# ArduinoSmarticle.net
KiCad netlist of a schematic drawn in EAGLE
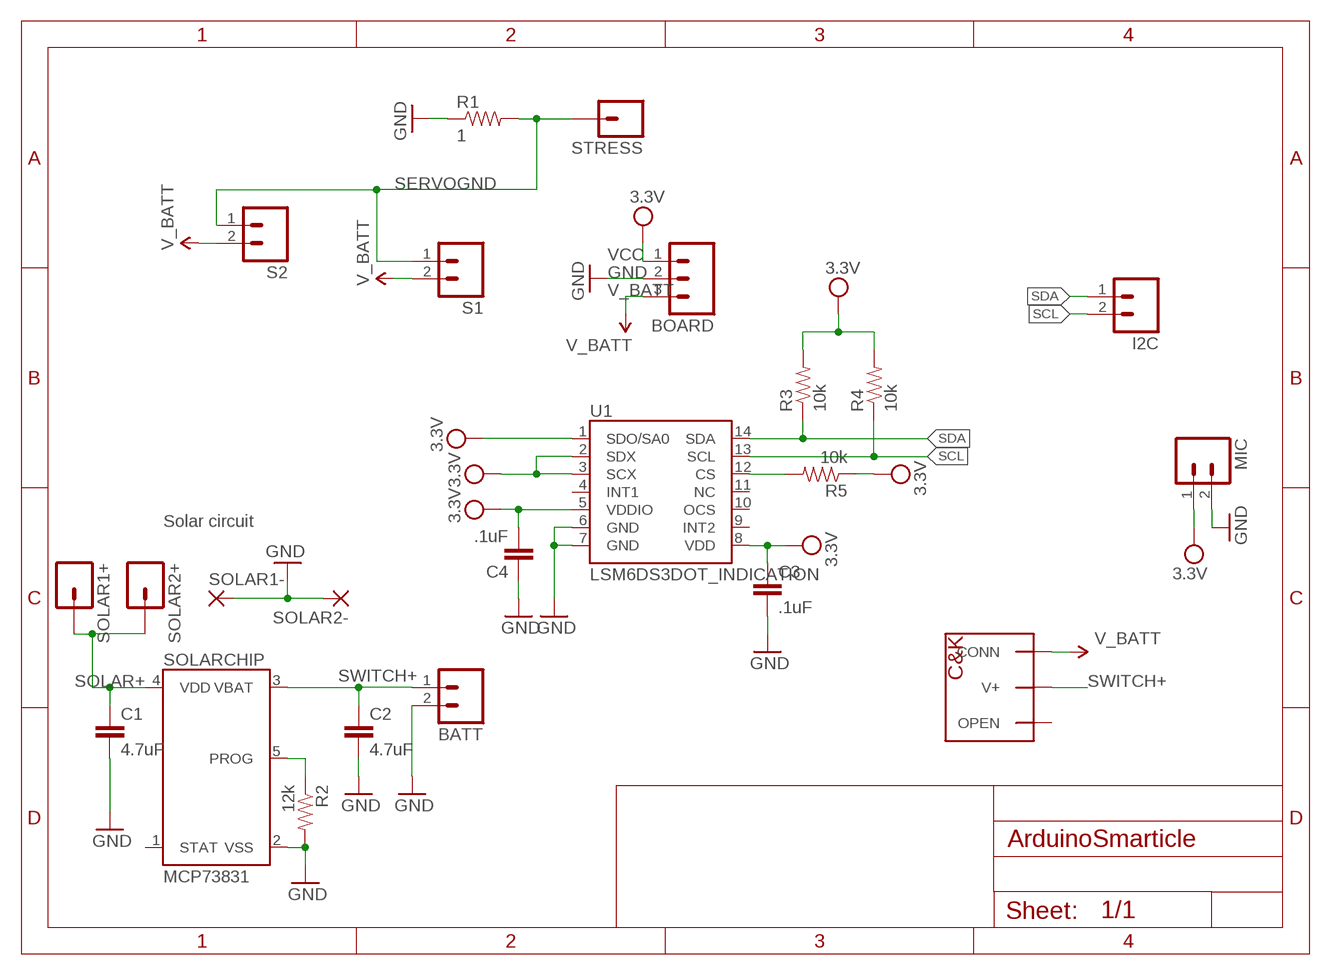
[diagram p0: schematic, sheet 1]

(export (version "E")
  (design (tool "Eeschema 10.0.6"))
  (components
    (comp (ref "BATT")
      (value "M02PTH")
      (footprint "eagle-import:1X02")
      (libsource (lib "eagle-import") (part "M02PTH"))
    )
    (comp (ref "BOARD")
      (value "M03PTH")
      (footprint "eagle-import:1X03")
      (libsource (lib "eagle-import") (part "M03PTH"))
    )
    (comp (ref "C1")
      (value "4.7uF")
      (footprint "eagle-import:0603-CAP")
      (libsource (lib "eagle-import") (part "4.7UF-6.3V-10%(0603)0603"))
    )
    (comp (ref "C2")
      (value "4.7uF")
      (footprint "eagle-import:0603-CAP")
      (libsource (lib "eagle-import") (part "4.7UF-6.3V-10%(0603)0603"))
    )
    (comp (ref "C3")
      (value ".1uF")
      (footprint "eagle-import:0603-CAP")
      (libsource (lib "eagle-import") (part "4.7UF-6.3V-10%(0603)0603"))
    )
    (comp (ref "C4")
      (value ".1uF")
      (footprint "eagle-import:0603-CAP")
      (libsource (lib "eagle-import") (part "4.7UF-6.3V-10%(0603)0603"))
    )
    (comp (ref "I2C")
      (value "M02PTH")
      (footprint "eagle-import:1X02")
      (libsource (lib "eagle-import") (part "M02PTH"))
    )
    (comp (ref "MIC")
      (value "M02PTH")
      (footprint "eagle-import:1X02")
      (libsource (lib "eagle-import") (part "M02PTH"))
    )
    (comp (ref "R1")
      (value "1")
      (footprint "eagle-import:0603-RES")
      (libsource (lib "eagle-import") (part "2.0KOHM1/10W5%(0603)"))
    )
    (comp (ref "R2")
      (value "12k")
      (footprint "eagle-import:0603")
      (libsource (lib "eagle-import") (part "10.5KOHM1/10W1%(0603)"))
    )
    (comp (ref "R3")
      (value "10k")
      (footprint "eagle-import:0603-RES")
      (libsource (lib "eagle-import") (part "4.7KOHM-1/10W-1%(0603)"))
    )
    (comp (ref "R4")
      (value "10k")
      (footprint "eagle-import:0603-RES")
      (libsource (lib "eagle-import") (part "4.7KOHM-1/10W-1%(0603)"))
    )
    (comp (ref "R5")
      (value "10k")
      (footprint "eagle-import:0603-RES")
      (libsource (lib "eagle-import") (part "4.7KOHM-1/10W-1%(0603)"))
    )
    (comp (ref "S1")
      (value "M02PTH")
      (footprint "eagle-import:1X02")
      (libsource (lib "eagle-import") (part "M02PTH"))
    )
    (comp (ref "S2")
      (value "M02PTH")
      (footprint "eagle-import:1X02")
      (libsource (lib "eagle-import") (part "M02PTH"))
    )
    (comp (ref "SOLAR1+")
      (value "M01PTH")
      (footprint "eagle-import:1X01")
      (libsource (lib "eagle-import") (part "M01PTH"))
    )
    (comp (ref "SOLAR1-")
      (value "1,6/0,9")
      (footprint "eagle-import:1,6_0,9")
      (libsource (lib "eagle-import") (part "1,6/0,9"))
    )
    (comp (ref "SOLAR2+")
      (value "M01PTH")
      (footprint "eagle-import:1X01")
      (libsource (lib "eagle-import") (part "M01PTH"))
    )
    (comp (ref "SOLAR2-")
      (value "1,6/0,9")
      (footprint "eagle-import:1,6_0,9")
      (libsource (lib "eagle-import") (part "1,6/0,9"))
    )
    (comp (ref "SOLARCHIP")
      (value "MCP73831")
      (footprint "eagle-import:SOT23-5")
      (libsource (lib "eagle-import") (part "MCP73831"))
    )
    (comp (ref "STRESS")
      (value "M01PTH")
      (footprint "eagle-import:1X01")
      (libsource (lib "eagle-import") (part "M01PTH"))
    )
    (comp (ref "U$1")
      (value "WILL-BLACKSLIDESWITCH")
      (footprint "eagle-import:WILL-BLACKSLIDESWITCH")
      (libsource (lib "eagle-import") (part "WILL-BLACKSLIDESWITCH"))
    )
    (comp (ref "U1")
      (value "LSM6DS3DOT_INDICATION")
      (footprint "eagle-import:LGA14L_DOT_INDICATOR")
      (libsource (lib "eagle-import") (part "LSM6DS3DOT_INDICATION"))
    )
  )
  (nets
    (net (code "1") (name "/SERVOGND") (class "Default")
      (node (ref "R1") (pin "2") (pinfunction "2_2") (pintype "passive"))
      (node (ref "S1") (pin "1") (pinfunction "1_1") (pintype "passive"))
      (node (ref "S2") (pin "1") (pinfunction "1_1") (pintype "passive"))
      (node (ref "STRESS") (pin "1") (pinfunction "1_1") (pintype "passive"))
    )
    (net (code "2") (name "/SOLAR+") (class "Default")
      (node (ref "C1") (pin "1") (pinfunction "1_1") (pintype "passive"))
      (node (ref "SOLAR1+") (pin "1") (pinfunction "1_1") (pintype "passive"))
      (node (ref "SOLAR2+") (pin "1") (pinfunction "1_1") (pintype "passive"))
      (node (ref "SOLARCHIP") (pin "4") (pinfunction "VDD_4") (pintype "power_in"))
    )
    (net (code "3") (name "/SWITCH+") (class "Default")
      (node (ref "BATT") (pin "1") (pinfunction "1_1") (pintype "passive"))
      (node (ref "C2") (pin "1") (pinfunction "1_1") (pintype "passive"))
      (node (ref "SOLARCHIP") (pin "3") (pinfunction "VBAT_3") (pintype "power_in"))
      (node (ref "U$1") (pin "V+") (pinfunction "V+_V+") (pintype "bidirectional"))
    )
    (net (code "4") (name "3.3V") (class "Default")
      (node (ref "BOARD") (pin "1") (pinfunction "1_1") (pintype "passive"))
      (node (ref "C3") (pin "1") (pinfunction "1_1") (pintype "passive"))
      (node (ref "C4") (pin "2") (pinfunction "2_2") (pintype "passive"))
      (node (ref "MIC") (pin "1") (pinfunction "1_1") (pintype "passive"))
      (node (ref "R3") (pin "2") (pinfunction "2_2") (pintype "passive"))
      (node (ref "R4") (pin "2") (pinfunction "2_2") (pintype "passive"))
      (node (ref "R5") (pin "1") (pinfunction "1_1") (pintype "passive"))
      (node (ref "U1") (pin "1") (pinfunction "SDO/SA0_1") (pintype "bidirectional"))
      (node (ref "U1") (pin "2") (pinfunction "SDX_2") (pintype "bidirectional"))
      (node (ref "U1") (pin "3") (pinfunction "SCX_3") (pintype "bidirectional"))
      (node (ref "U1") (pin "5") (pinfunction "VDDIO_5") (pintype "bidirectional"))
      (node (ref "U1") (pin "8") (pinfunction "VDD_8") (pintype "bidirectional"))
    )
    (net (code "5") (name "GND") (class "Default")
      (node (ref "BATT") (pin "2") (pinfunction "2_2") (pintype "passive"))
      (node (ref "BOARD") (pin "2") (pinfunction "2_2") (pintype "passive"))
      (node (ref "C1") (pin "2") (pinfunction "2_2") (pintype "passive"))
      (node (ref "C2") (pin "2") (pinfunction "2_2") (pintype "passive"))
      (node (ref "C3") (pin "2") (pinfunction "2_2") (pintype "passive"))
      (node (ref "C4") (pin "1") (pinfunction "1_1") (pintype "passive"))
      (node (ref "MIC") (pin "2") (pinfunction "2_2") (pintype "passive"))
      (node (ref "R1") (pin "1") (pinfunction "1_1") (pintype "passive"))
      (node (ref "R2") (pin "2") (pinfunction "2_2") (pintype "passive"))
      (node (ref "SOLAR1-") (pin "1") (pinfunction "P_1") (pintype "passive"))
      (node (ref "SOLAR2-") (pin "1") (pinfunction "P_1") (pintype "passive"))
      (node (ref "SOLARCHIP") (pin "2") (pinfunction "VSS_2") (pintype "power_in"))
      (node (ref "U1") (pin "6") (pinfunction "GND_6") (pintype "bidirectional"))
      (node (ref "U1") (pin "7") (pinfunction "GND_7") (pintype "bidirectional"))
    )
    (net (code "6") (name "Net-(SOLARCHIP-PROG)") (class "Default")
      (node (ref "R2") (pin "1") (pinfunction "1_1") (pintype "passive"))
      (node (ref "SOLARCHIP") (pin "5") (pinfunction "PROG_5") (pintype "input"))
    )
    (net (code "7") (name "Net-(U1-CS)") (class "Default")
      (node (ref "R5") (pin "2") (pinfunction "2_2") (pintype "passive"))
      (node (ref "U1") (pin "12") (pinfunction "CS_12") (pintype "bidirectional"))
    )
    (net (code "8") (name "SCL") (class "Default")
      (node (ref "I2C") (pin "2") (pinfunction "2_2") (pintype "passive"))
      (node (ref "R4") (pin "1") (pinfunction "1_1") (pintype "passive"))
      (node (ref "U1") (pin "13") (pinfunction "SCL_13") (pintype "bidirectional"))
    )
    (net (code "9") (name "SDA") (class "Default")
      (node (ref "I2C") (pin "1") (pinfunction "1_1") (pintype "passive"))
      (node (ref "R3") (pin "1") (pinfunction "1_1") (pintype "passive"))
      (node (ref "U1") (pin "14") (pinfunction "SDA_14") (pintype "bidirectional"))
    )
    (net (code "10") (name "V_BATT") (class "Default")
      (node (ref "BOARD") (pin "3") (pinfunction "3_3") (pintype "passive"))
      (node (ref "S1") (pin "2") (pinfunction "2_2") (pintype "passive"))
      (node (ref "S2") (pin "2") (pinfunction "2_2") (pintype "passive"))
      (node (ref "U$1") (pin "CONN") (pinfunction "CONN_CONN") (pintype "bidirectional"))
    )
    (net (code "11") (name "unconnected-(SOLARCHIP-STAT-Pad1)") (class "Default")
      (node (ref "SOLARCHIP") (pin "1") (pinfunction "STAT_1") (pintype "output"))
    )
    (net (code "12") (name "unconnected-(U$1-OPEN-PadNC)") (class "Default")
      (node (ref "U$1") (pin "NC") (pinfunction "OPEN_NC") (pintype "bidirectional"))
    )
    (net (code "13") (name "unconnected-(U1-INT1-Pad4)") (class "Default")
      (node (ref "U1") (pin "4") (pinfunction "INT1_4") (pintype "bidirectional"))
    )
    (net (code "14") (name "unconnected-(U1-INT2-Pad9)") (class "Default")
      (node (ref "U1") (pin "9") (pinfunction "INT2_9") (pintype "bidirectional"))
    )
    (net (code "15") (name "unconnected-(U1-NC-Pad11)") (class "Default")
      (node (ref "U1") (pin "11") (pinfunction "NC_11") (pintype "bidirectional"))
    )
    (net (code "16") (name "unconnected-(U1-OCS-Pad10)") (class "Default")
      (node (ref "U1") (pin "10") (pinfunction "OCS_10") (pintype "bidirectional"))
    )
  )
)
